# TMS320F28379D_Interfaz.net
KiCad netlist of a schematic drawn in Altium Designer
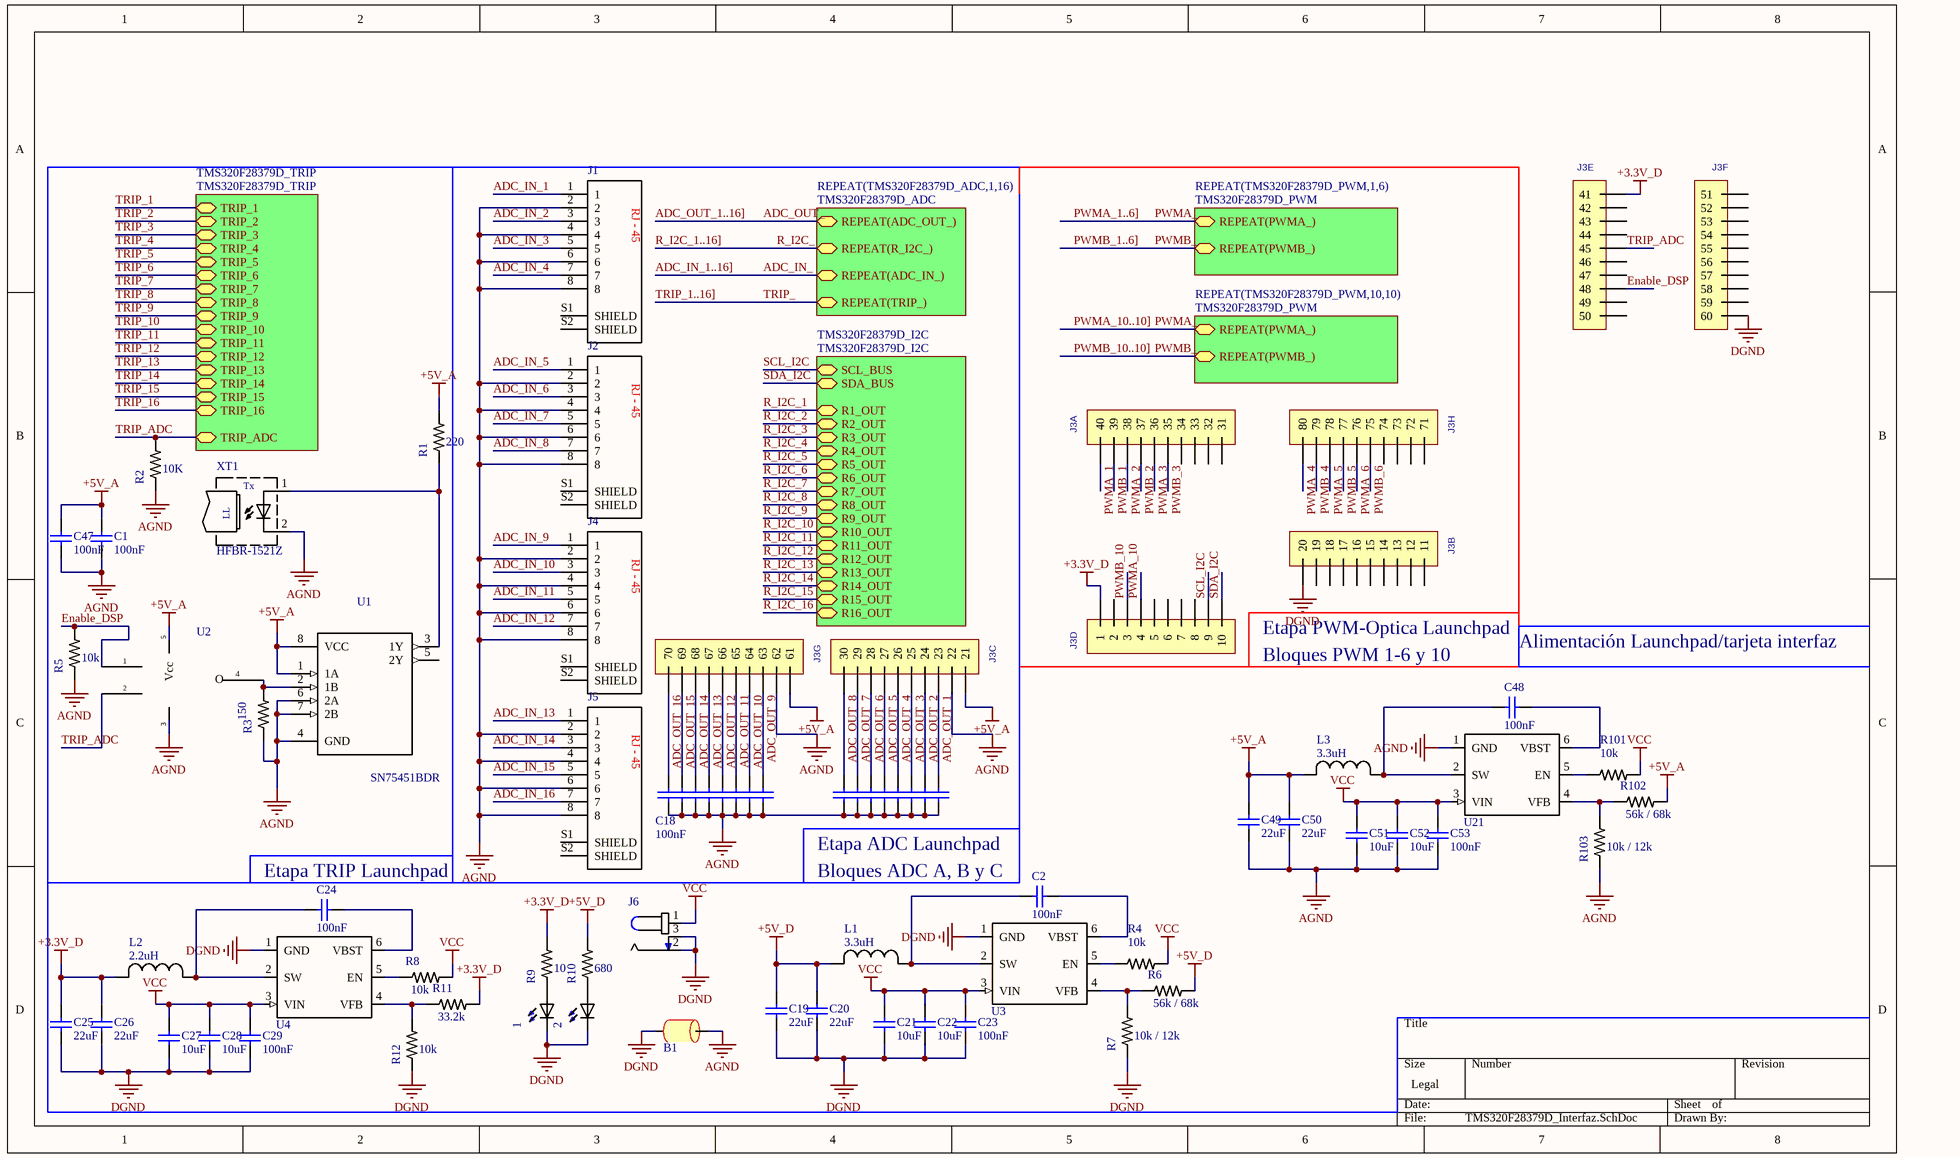
[diagram p0: TMS320F28379D_Interfaz.SchDoc]

(export (version "E")
  (design (tool "Eeschema 10.0.6"))
  (components
    (comp (ref "1")
      (value "LED")
      (footprint "LED_0805")
      (description "Led")
      (fields
        (field (name "DIGI-KEY PART NUMBER") "732-4984-1-ND")
        (field (name "MANUFACTURER PART NUMBER") "150080RS75000")
      )
      (libsource (lib "Fibras Opticas") (part "LED"))
    )
    (comp (ref "2")
      (value "LED")
      (footprint "LED_0805")
      (description "Led")
      (fields
        (field (name "DIGI-KEY PART NUMBER") "732-4984-1-ND")
        (field (name "MANUFACTURER PART NUMBER") "150080RS75000")
      )
      (libsource (lib "Fibras Opticas") (part "LED"))
    )
    (comp (ref "B1")
      (value "Bead")
      (footprint "1206")
      (description "Ferrite bead")
      (fields
        (field (name "DIGI-KEY PART NUMBER") "490-1055-1-ND")
        (field (name "MANUFACTURER PART NUMBER") "BLM31PG500SN1L")
      )
      (libsource (lib "Inductores") (part "Bead"))
    )
    (comp (ref "C1")
      (value "100nF")
      (footprint "CAP 0805")
      (fields (field (name "Comment") "Cap cerámico"))
      (libsource (lib "Condensadores") (part "Cap cerámico"))
    )
    (comp (ref "C2")
      (value "100nF")
      (footprint "CAP 0805")
      (fields (field (name "Comment") "Cap cerámico"))
      (libsource (lib "Condensadores") (part "Cap cerámico"))
    )
    (comp (ref "C3")
      (value "Cap cerámico")
      (footprint "CAP 0805")
      (libsource (lib "Condensadores") (part "Cap cerámico"))
    )
    (comp (ref "C4")
      (value "Cap cerámico")
      (footprint "CAP 0805")
      (libsource (lib "Condensadores") (part "Cap cerámico"))
    )
    (comp (ref "C5")
      (value "Cap cerámico")
      (footprint "CAP 0805")
      (libsource (lib "Condensadores") (part "Cap cerámico"))
    )
    (comp (ref "C6")
      (value "Cap cerámico")
      (footprint "CAP 0805")
      (libsource (lib "Condensadores") (part "Cap cerámico"))
    )
    (comp (ref "C7")
      (value "Cap cerámico")
      (footprint "CAP 0805")
      (libsource (lib "Condensadores") (part "Cap cerámico"))
    )
    (comp (ref "C8")
      (value "Cap cerámico")
      (footprint "CAP 0805")
      (libsource (lib "Condensadores") (part "Cap cerámico"))
    )
    (comp (ref "C9")
      (value "Cap cerámico")
      (footprint "CAP 0805")
      (libsource (lib "Condensadores") (part "Cap cerámico"))
    )
    (comp (ref "C10")
      (value "Cap cerámico")
      (footprint "CAP 0805")
      (libsource (lib "Condensadores") (part "Cap cerámico"))
    )
    (comp (ref "C11")
      (value "Cap cerámico")
      (footprint "CAP 0805")
      (libsource (lib "Condensadores") (part "Cap cerámico"))
    )
    (comp (ref "C12")
      (value "Cap cerámico")
      (footprint "CAP 0805")
      (libsource (lib "Condensadores") (part "Cap cerámico"))
    )
    (comp (ref "C13")
      (value "Cap cerámico")
      (footprint "CAP 0805")
      (libsource (lib "Condensadores") (part "Cap cerámico"))
    )
    (comp (ref "C14")
      (value "Cap cerámico")
      (footprint "CAP 0805")
      (libsource (lib "Condensadores") (part "Cap cerámico"))
    )
    (comp (ref "C15")
      (value "Cap cerámico")
      (footprint "CAP 0805")
      (libsource (lib "Condensadores") (part "Cap cerámico"))
    )
    (comp (ref "C16")
      (value "Cap cerámico")
      (footprint "CAP 0805")
      (libsource (lib "Condensadores") (part "Cap cerámico"))
    )
    (comp (ref "C17")
      (value "Cap cerámico")
      (footprint "CAP 0805")
      (libsource (lib "Condensadores") (part "Cap cerámico"))
    )
    (comp (ref "C18")
      (value "100nF")
      (footprint "CAP 0805")
      (fields (field (name "Comment") "Cap cerámico"))
      (libsource (lib "Condensadores") (part "Cap cerámico"))
    )
    (comp (ref "C19")
      (value "22uF")
      (footprint "CAP 1206")
      (fields (field (name "Comment") "Cap cerámico"))
      (libsource (lib "Condensadores") (part "Cap cerámico"))
    )
    (comp (ref "C20")
      (value "22uF")
      (footprint "CAP 1206")
      (fields (field (name "Comment") "Cap cerámico"))
      (libsource (lib "Condensadores") (part "Cap cerámico"))
    )
    (comp (ref "C21")
      (value "10uF")
      (footprint "CAP 1206")
      (fields (field (name "Comment") "Cap cerámico"))
      (libsource (lib "Condensadores") (part "Cap cerámico"))
    )
    (comp (ref "C22")
      (value "10uF")
      (footprint "CAP 1206")
      (fields (field (name "Comment") "Cap cerámico"))
      (libsource (lib "Condensadores") (part "Cap cerámico"))
    )
    (comp (ref "C23")
      (value "100nF")
      (footprint "CAP 0805")
      (fields (field (name "Comment") "Cap cerámico"))
      (libsource (lib "Condensadores") (part "Cap cerámico"))
    )
    (comp (ref "C24")
      (value "100nF")
      (footprint "CAP 0805")
      (fields (field (name "Comment") "Cap cerámico"))
      (libsource (lib "Condensadores") (part "Cap cerámico"))
    )
    (comp (ref "C25")
      (value "22uF")
      (footprint "CAP 1206")
      (fields (field (name "Comment") "Cap cerámico"))
      (libsource (lib "Condensadores") (part "Cap cerámico"))
    )
    (comp (ref "C26")
      (value "22uF")
      (footprint "CAP 1206")
      (fields (field (name "Comment") "Cap cerámico"))
      (libsource (lib "Condensadores") (part "Cap cerámico"))
    )
    (comp (ref "C27")
      (value "10uF")
      (footprint "CAP 1206")
      (fields (field (name "Comment") "Cap cerámico"))
      (libsource (lib "Condensadores") (part "Cap cerámico"))
    )
    (comp (ref "C28")
      (value "10uF")
      (footprint "CAP 1206")
      (fields (field (name "Comment") "Cap cerámico"))
      (libsource (lib "Condensadores") (part "Cap cerámico"))
    )
    (comp (ref "C29")
      (value "100nF")
      (footprint "CAP 0805")
      (fields (field (name "Comment") "Cap cerámico"))
      (libsource (lib "Condensadores") (part "Cap cerámico"))
    )
    (comp (ref "C47")
      (value "100nF")
      (footprint "CAP 0805")
      (fields (field (name "Comment") "Cap cerámico"))
      (libsource (lib "Condensadores") (part "Cap cerámico"))
    )
    (comp (ref "C48")
      (value "100nF")
      (footprint "CAP 0805")
      (fields (field (name "Comment") "Cap cerámico"))
      (libsource (lib "Condensadores") (part "Cap cerámico"))
    )
    (comp (ref "C49")
      (value "22uF")
      (footprint "CAP 1206")
      (fields (field (name "Comment") "Cap cerámico"))
      (libsource (lib "Condensadores") (part "Cap cerámico"))
    )
    (comp (ref "C50")
      (value "22uF")
      (footprint "CAP 1206")
      (fields (field (name "Comment") "Cap cerámico"))
      (libsource (lib "Condensadores") (part "Cap cerámico"))
    )
    (comp (ref "C51")
      (value "10uF")
      (footprint "CAP 1206")
      (fields (field (name "Comment") "Cap cerámico"))
      (libsource (lib "Condensadores") (part "Cap cerámico"))
    )
    (comp (ref "C52")
      (value "10uF")
      (footprint "CAP 1206")
      (fields (field (name "Comment") "Cap cerámico"))
      (libsource (lib "Condensadores") (part "Cap cerámico"))
    )
    (comp (ref "C53")
      (value "100nF")
      (footprint "CAP 0805")
      (fields (field (name "Comment") "Cap cerámico"))
      (libsource (lib "Condensadores") (part "Cap cerámico"))
    )
    (comp (ref "J1")
      (value "Ethernet TH")
      (footprint "ETHERNET TH")
      (description "CONN MOD JACK 8P8C VERT SHIELDED")
      (fields
        (field (name "DIGI-KEY PART NUMBER") "A31430-ND")
        (field (name "MANUFACTURER PART NUMBER") "5557969-1")
      )
      (libsource (lib "Conectores") (part "Ethernet TH"))
    )
    (comp (ref "J2")
      (value "Ethernet TH")
      (footprint "ETHERNET TH")
      (description "CONN MOD JACK 8P8C VERT SHIELDED")
      (fields
        (field (name "DIGI-KEY PART NUMBER") "A31430-ND")
        (field (name "MANUFACTURER PART NUMBER") "5557969-1")
      )
      (libsource (lib "Conectores") (part "Ethernet TH"))
    )
    (comp (ref "J3")
      (value "Header 20pin")
      (footprint "Header 20pin_TMS320F28379D")
      (fields
        (field (name "DIGI-KEY PART NUMBER") "609-3221-ND")
        (field (name "MANUFACTURER PART NUMBER") "67996-420HLF")
      )
      (libsource (lib "Conectores") (part "Header 20pin"))
    )
    (comp (ref "J4")
      (value "Ethernet TH")
      (footprint "ETHERNET TH")
      (description "CONN MOD JACK 8P8C VERT SHIELDED")
      (fields
        (field (name "DIGI-KEY PART NUMBER") "A31430-ND")
        (field (name "MANUFACTURER PART NUMBER") "5557969-1")
      )
      (libsource (lib "Conectores") (part "Ethernet TH"))
    )
    (comp (ref "J5")
      (value "Ethernet TH")
      (footprint "ETHERNET TH")
      (description "CONN MOD JACK 8P8C VERT SHIELDED")
      (fields
        (field (name "DIGI-KEY PART NUMBER") "A31430-ND")
        (field (name "MANUFACTURER PART NUMBER") "5557969-1")
      )
      (libsource (lib "Conectores") (part "Ethernet TH"))
    )
    (comp (ref "J6")
      (value "694106301002")
      (footprint "Power Jack DC")
      (description "Connector, Power Entry, Jack, 3a, 20vdc")
      (fields (field (name "DIGI-KEY PART NUMBER") "732-5930-ND"))
      (libsource (lib "Conectores") (part "Power Jack"))
    )
    (comp (ref "L1")
      (value "3.3uH")
      (footprint "Inductor 3.3uH")
      (description "Inductor")
      (fields
        (field (name "DIGI-KEY PART NUMBER") "732-1152-1-ND")
        (field (name "MANUFACTURER PART NUMBER") "744311330")
      )
      (libsource (lib "Inductores") (part "Inductor 3.3uH"))
    )
    (comp (ref "L2")
      (value "2.2uH")
      (footprint "Inductor 3.3uH")
      (description "Inductor")
      (fields
        (field (name "DIGI-KEY PART NUMBER") "732-1151-1-ND")
        (field (name "MANUFACTURER PART NUMBER") "744311220")
      )
      (libsource (lib "Inductores") (part "Inductor 2.2uH"))
    )
    (comp (ref "L3")
      (value "3.3uH")
      (footprint "Inductor 3.3uH")
      (description "Inductor")
      (fields
        (field (name "DIGI-KEY PART NUMBER") "732-1152-1-ND")
        (field (name "MANUFACTURER PART NUMBER") "744311330")
      )
      (libsource (lib "Inductores") (part "Inductor 3.3uH"))
    )
    (comp (ref "R1")
      (value "220")
      (footprint "Resistor 0805")
      (description "Resistor")
      (fields (field (name "Comment") "Resistor 0805"))
      (libsource (lib "Resistencias") (part "Resistor"))
    )
    (comp (ref "R2")
      (value "10K")
      (footprint "Resistor 0805")
      (description "Resistor")
      (fields (field (name "Comment") "Resistor 0805"))
      (libsource (lib "Resistencias") (part "Resistor"))
    )
    (comp (ref "R3")
      (value "150")
      (footprint "Resistor 0805")
      (description "Resistor")
      (fields (field (name "Comment") "Resistor 0805"))
      (libsource (lib "Resistencias") (part "Resistor"))
    )
    (comp (ref "R4")
      (value "10k")
      (footprint "Resistor 0805")
      (description "Resistor")
      (fields (field (name "Comment") "Resistor 0805"))
      (libsource (lib "Resistencias") (part "Resistor"))
    )
    (comp (ref "R5")
      (value "10k")
      (footprint "Resistor 0805")
      (description "Resistor")
      (fields (field (name "Comment") "Resistor 0805"))
      (libsource (lib "Resistencias") (part "Resistor"))
    )
    (comp (ref "R6")
      (value "56k / 68k")
      (footprint "Resistor 0805")
      (description "Resistor")
      (fields (field (name "Comment") "Resistor 0805"))
      (libsource (lib "Resistencias") (part "Resistor"))
    )
    (comp (ref "R7")
      (value "10k / 12k")
      (footprint "Resistor 0805")
      (description "Resistor")
      (fields (field (name "Comment") "Resistor 0805"))
      (libsource (lib "Resistencias") (part "Resistor"))
    )
    (comp (ref "R8")
      (value "10k")
      (footprint "Resistor 0805")
      (description "Resistor")
      (fields (field (name "Comment") "Resistor 0805"))
      (libsource (lib "Resistencias") (part "Resistor"))
    )
    (comp (ref "R9")
      (value "10")
      (footprint "Resistor 0805")
      (description "Resistor")
      (fields (field (name "Comment") "Resistor 0805"))
      (libsource (lib "Resistencias") (part "Resistor"))
    )
    (comp (ref "R10")
      (value "680")
      (footprint "Resistor 0805")
      (description "Resistor")
      (fields (field (name "Comment") "Resistor 0805"))
      (libsource (lib "Resistencias") (part "Resistor"))
    )
    (comp (ref "R11")
      (value "33.2k")
      (footprint "Resistor 0805")
      (description "Resistor")
      (fields (field (name "Comment") "Resistor 0805"))
      (libsource (lib "Resistencias") (part "Resistor"))
    )
    (comp (ref "R12")
      (value "10k")
      (footprint "Resistor 0805")
      (description "Resistor")
      (fields (field (name "Comment") "Resistor 0805"))
      (libsource (lib "Resistencias") (part "Resistor"))
    )
    (comp (ref "R101")
      (value "10k")
      (footprint "Resistor 0805")
      (description "Resistor")
      (fields (field (name "Comment") "Resistor 0805"))
      (libsource (lib "Resistencias") (part "Resistor"))
    )
    (comp (ref "R102")
      (value "56k / 68k")
      (footprint "Resistor 0805")
      (description "Resistor")
      (fields (field (name "Comment") "Resistor 0805"))
      (libsource (lib "Resistencias") (part "Resistor"))
    )
    (comp (ref "R103")
      (value "10k / 12k")
      (footprint "Resistor 0805")
      (description "Resistor")
      (fields (field (name "Comment") "Resistor 0805"))
      (libsource (lib "Resistencias") (part "Resistor"))
    )
    (comp (ref "U1")
      (value "SN75451BDR")
      (footprint "8-SOIC")
      (description "Dual Very-High Speed, High-Current Peripheral Drivers 8-SOIC 0 to 70")
      (fields (field (name "DIGI-KEY PART NUMBER") "296-14960-6-ND"))
      (libsource (lib "Circuitos integrados") (part "SN75451BDR"))
    )
    (comp (ref "U2")
      (value "NOR MC74VHC1G02DFT2G")
      (footprint "SOT-553")
      (description "NOR Gate IC 1 Channel SC-88A (SC-70-5/SOT-353)")
      (fields
        (field (name "DIGI-KEY PART NUMBER") "MC74VHC1G02DFT2GOSCT-ND")
        (field (name "MANUFACTURER PART NUMBER") "MC74VHC1G02DFT2G")
      )
      (libsource (lib "Circuitos integrados") (part "NOR MC74VHC1G02DFT2G"))
    )
    (comp (ref "U3")
      (value "TPS565201DDCR")
      (footprint "6-SOT-23")
      (description "Buck 5A")
      (fields (field (name "DIGI-KEY PART NUMBER") "296-49006-1-ND"))
      (libsource (lib "Circuitos integrados") (part "TPS565201DDCR"))
    )
    (comp (ref "U4")
      (value "TPS565201DDCR")
      (footprint "6-SOT-23")
      (description "Buck 5A")
      (fields (field (name "DIGI-KEY PART NUMBER") "296-49006-1-ND"))
      (libsource (lib "Circuitos integrados") (part "TPS565201DDCR"))
    )
    (comp (ref "U21")
      (value "TPS565201DDCR")
      (footprint "6-SOT-23")
      (description "Buck 5A")
      (fields (field (name "DIGI-KEY PART NUMBER") "296-49006-1-ND"))
      (libsource (lib "Circuitos integrados") (part "TPS565201DDCR"))
    )
    (comp (ref "XT1")
      (value "HFBR-1521Z")
      (footprint "HFBR-15X1Z")
      (fields (field (name "DIGI-KEY PART NUMBER") "516-2043-ND"))
      (libsource (lib "Fibras Opticas") (part "HFBR-1521Z"))
    )
  )
  (nets
    (net (code "9") (name "+3.3V_D") (class "Default")
      (node (ref "C25") (pin "2") (pinfunction "2_2") (pintype "passive"))
      (node (ref "C26") (pin "2") (pinfunction "2_2") (pintype "passive"))
      (node (ref "J3") (pin "1") (pinfunction "1_1") (pintype "passive"))
      (node (ref "J3") (pin "41") (pinfunction "41_41") (pintype "passive"))
      (node (ref "L2") (pin "2") (pinfunction "2_2") (pintype "passive"))
      (node (ref "R11") (pin "2") (pinfunction "2_2") (pintype "passive"))
      (node (ref "R9") (pin "2") (pinfunction "2_2") (pintype "passive"))
    )
    (net (code "10") (name "+5V_A") (class "Default")
      (node (ref "C1") (pin "2") (pinfunction "2_2") (pintype "passive"))
      (node (ref "C47") (pin "2") (pinfunction "2_2") (pintype "passive"))
      (node (ref "C49") (pin "2") (pinfunction "2_2") (pintype "passive"))
      (node (ref "C50") (pin "2") (pinfunction "2_2") (pintype "passive"))
      (node (ref "J3") (pin "21") (pinfunction "21_21") (pintype "passive"))
      (node (ref "J3") (pin "61") (pinfunction "61_61") (pintype "passive"))
      (node (ref "L3") (pin "2") (pinfunction "2_2") (pintype "passive"))
      (node (ref "R1") (pin "2") (pinfunction "2_2") (pintype "passive"))
      (node (ref "R102") (pin "2") (pinfunction "2_2") (pintype "passive"))
      (node (ref "U1") (pin "1") (pinfunction "1A_1") (pintype "input"))
      (node (ref "U1") (pin "8") (pinfunction "VCC_8") (pintype "power_in"))
      (node (ref "U2") (pin "5") (pinfunction "Vcc_5") (pintype "passive"))
    )
    (net (code "11") (name "+5V_D") (class "Default")
      (node (ref "C19") (pin "2") (pinfunction "2_2") (pintype "passive"))
      (node (ref "C20") (pin "2") (pinfunction "2_2") (pintype "passive"))
      (node (ref "L1") (pin "2") (pinfunction "2_2") (pintype "passive"))
      (node (ref "R10") (pin "2") (pinfunction "2_2") (pintype "passive"))
      (node (ref "R6") (pin "2") (pinfunction "2_2") (pintype "passive"))
    )
    (net (code "13") (name "/ADC_IN_1") (class "Default")
      (node (ref "J1") (pin "1") (pinfunction "1_1") (pintype "passive"))
    )
    (net (code "14") (name "/ADC_IN_2") (class "Default")
      (node (ref "J1") (pin "3") (pinfunction "3_3") (pintype "passive"))
    )
    (net (code "15") (name "/ADC_IN_3") (class "Default")
      (node (ref "J1") (pin "5") (pinfunction "5_5") (pintype "passive"))
    )
    (net (code "16") (name "/ADC_IN_4") (class "Default")
      (node (ref "J1") (pin "7") (pinfunction "7_7") (pintype "passive"))
    )
    (net (code "17") (name "/ADC_IN_5") (class "Default")
      (node (ref "J2") (pin "1") (pinfunction "1_1") (pintype "passive"))
    )
    (net (code "18") (name "/ADC_IN_6") (class "Default")
      (node (ref "J2") (pin "3") (pinfunction "3_3") (pintype "passive"))
    )
    (net (code "19") (name "/ADC_IN_7") (class "Default")
      (node (ref "J2") (pin "5") (pinfunction "5_5") (pintype "passive"))
    )
    (net (code "20") (name "/ADC_IN_8") (class "Default")
      (node (ref "J2") (pin "7") (pinfunction "7_7") (pintype "passive"))
    )
    (net (code "21") (name "/ADC_IN_9") (class "Default")
      (node (ref "J4") (pin "1") (pinfunction "1_1") (pintype "passive"))
    )
    (net (code "22") (name "/ADC_IN_10") (class "Default")
      (node (ref "J4") (pin "3") (pinfunction "3_3") (pintype "passive"))
    )
    (net (code "23") (name "/ADC_IN_11") (class "Default")
      (node (ref "J4") (pin "5") (pinfunction "5_5") (pintype "passive"))
    )
    (net (code "24") (name "/ADC_IN_12") (class "Default")
      (node (ref "J4") (pin "7") (pinfunction "7_7") (pintype "passive"))
    )
    (net (code "25") (name "/ADC_IN_13") (class "Default")
      (node (ref "J5") (pin "1") (pinfunction "1_1") (pintype "passive"))
    )
    (net (code "26") (name "/ADC_IN_14") (class "Default")
      (node (ref "J5") (pin "3") (pinfunction "3_3") (pintype "passive"))
    )
    (net (code "27") (name "/ADC_IN_15") (class "Default")
      (node (ref "J5") (pin "5") (pinfunction "5_5") (pintype "passive"))
    )
    (net (code "28") (name "/ADC_IN_16") (class "Default")
      (node (ref "J5") (pin "7") (pinfunction "7_7") (pintype "passive"))
    )
    (net (code "30") (name "/ADC_OUT_1") (class "Default")
      (node (ref "C17") (pin "1") (pinfunction "1_1") (pintype "passive"))
      (node (ref "J3") (pin "23") (pinfunction "23_23") (pintype "passive"))
    )
    (net (code "31") (name "/ADC_OUT_2") (class "Default")
      (node (ref "C16") (pin "1") (pinfunction "1_1") (pintype "passive"))
      (node (ref "J3") (pin "24") (pinfunction "24_24") (pintype "passive"))
    )
    (net (code "32") (name "/ADC_OUT_3") (class "Default")
      (node (ref "C15") (pin "1") (pinfunction "1_1") (pintype "passive"))
      (node (ref "J3") (pin "25") (pinfunction "25_25") (pintype "passive"))
    )
    (net (code "33") (name "/ADC_OUT_4") (class "Default")
      (node (ref "C14") (pin "1") (pinfunction "1_1") (pintype "passive"))
      (node (ref "J3") (pin "26") (pinfunction "26_26") (pintype "passive"))
    )
    (net (code "34") (name "/ADC_OUT_5") (class "Default")
      (node (ref "C13") (pin "1") (pinfunction "1_1") (pintype "passive"))
      (node (ref "J3") (pin "27") (pinfunction "27_27") (pintype "passive"))
    )
    (net (code "35") (name "/ADC_OUT_6") (class "Default")
      (node (ref "C12") (pin "1") (pinfunction "1_1") (pintype "passive"))
      (node (ref "J3") (pin "28") (pinfunction "28_28") (pintype "passive"))
    )
    (net (code "36") (name "/ADC_OUT_7") (class "Default")
      (node (ref "C11") (pin "1") (pinfunction "1_1") (pintype "passive"))
      (node (ref "J3") (pin "29") (pinfunction "29_29") (pintype "passive"))
    )
    (net (code "37") (name "/ADC_OUT_8") (class "Default")
      (node (ref "C10") (pin "1") (pinfunction "1_1") (pintype "passive"))
      (node (ref "J3") (pin "30") (pinfunction "30_30") (pintype "passive"))
    )
    (net (code "38") (name "/ADC_OUT_9") (class "Default")
      (node (ref "C9") (pin "1") (pinfunction "1_1") (pintype "passive"))
      (node (ref "J3") (pin "63") (pinfunction "63_63") (pintype "passive"))
    )
    (net (code "39") (name "/ADC_OUT_10") (class "Default")
      (node (ref "C8") (pin "1") (pinfunction "1_1") (pintype "passive"))
      (node (ref "J3") (pin "64") (pinfunction "64_64") (pintype "passive"))
    )
    (net (code "40") (name "/ADC_OUT_11") (class "Default")
      (node (ref "C7") (pin "1") (pinfunction "1_1") (pintype "passive"))
      (node (ref "J3") (pin "65") (pinfunction "65_65") (pintype "passive"))
    )
    (net (code "41") (name "/ADC_OUT_12") (class "Default")
      (node (ref "C6") (pin "1") (pinfunction "1_1") (pintype "passive"))
      (node (ref "J3") (pin "66") (pinfunction "66_66") (pintype "passive"))
    )
    (net (code "42") (name "/ADC_OUT_13") (class "Default")
      (node (ref "C5") (pin "1") (pinfunction "1_1") (pintype "passive"))
      (node (ref "J3") (pin "67") (pinfunction "67_67") (pintype "passive"))
    )
    (net (code "43") (name "/ADC_OUT_14") (class "Default")
      (node (ref "C4") (pin "1") (pinfunction "1_1") (pintype "passive"))
      (node (ref "J3") (pin "68") (pinfunction "68_68") (pintype "passive"))
    )
    (net (code "44") (name "/ADC_OUT_15") (class "Default")
      (node (ref "C3") (pin "1") (pinfunction "1_1") (pintype "passive"))
      (node (ref "J3") (pin "69") (pinfunction "69_69") (pintype "passive"))
    )
    (net (code "45") (name "/ADC_OUT_16") (class "Default")
      (node (ref "C18") (pin "2") (pinfunction "2_2") (pintype "passive"))
      (node (ref "J3") (pin "70") (pinfunction "70_70") (pintype "passive"))
    )
    (net (code "46") (name "/Enable_DSP") (class "Default")
      (node (ref "J3") (pin "48") (pinfunction "48_48") (pintype "passive"))
      (node (ref "R5") (pin "2") (pinfunction "2_2") (pintype "passive"))
      (node (ref "U2") (pin "1") (pinfunction "1_1") (pintype "passive"))
    )
    (net (code "48") (name "/PWMA_1") (class "Default")
      (node (ref "J3") (pin "40") (pinfunction "40_40") (pintype "passive"))
    )
    (net (code "49") (name "/PWMA_2") (class "Default")
      (node (ref "J3") (pin "38") (pinfunction "38_38") (pintype "passive"))
    )
    (net (code "50") (name "/PWMA_3") (class "Default")
      (node (ref "J3") (pin "36") (pinfunction "36_36") (pintype "passive"))
    )
    (net (code "51") (name "/PWMA_4") (class "Default")
      (node (ref "J3") (pin "80") (pinfunction "80_80") (pintype "passive"))
    )
    (net (code "52") (name "/PWMA_5") (class "Default")
      (node (ref "J3") (pin "78") (pinfunction "78_78") (pintype "passive"))
    )
    (net (code "53") (name "/PWMA_6") (class "Default")
      (node (ref "J3") (pin "76") (pinfunction "76_76") (pintype "passive"))
    )
    (net (code "54") (name "/PWMA_10") (class "Default")
      (node (ref "J3") (pin "4") (pinfunction "4_4") (pintype "passive"))
    )
    (net (code "56") (name "/PWMB_1") (class "Default")
      (node (ref "J3") (pin "39") (pinfunction "39_39") (pintype "passive"))
    )
    (net (code "57") (name "/PWMB_2") (class "Default")
      (node (ref "J3") (pin "37") (pinfunction "37_37") (pintype "passive"))
    )
    (net (code "58") (name "/PWMB_3") (class "Default")
      (node (ref "J3") (pin "35") (pinfunction "35_35") (pintype "passive"))
    )
    (net (code "59") (name "/PWMB_4") (class "Default")
      (node (ref "J3") (pin "79") (pinfunction "79_79") (pintype "passive"))
    )
    (net (code "60") (name "/PWMB_5") (class "Default")
      (node (ref "J3") (pin "77") (pinfunction "77_77") (pintype "passive"))
    )
    (net (code "61") (name "/PWMB_6") (class "Default")
      (node (ref "J3") (pin "75") (pinfunction "75_75") (pintype "passive"))
    )
    (net (code "62") (name "/PWMB_10") (class "Default")
      (node (ref "J3") (pin "3") (pinfunction "3_3") (pintype "passive"))
    )
    (net (code "80") (name "/SCL_I2C") (class "Default")
      (node (ref "J3") (pin "9") (pinfunction "9_9") (pintype "passive"))
    )
    (net (code "81") (name "/SDA_I2C") (class "Default")
      (node (ref "J3") (pin "10") (pinfunction "10_10") (pintype "passive"))
    )
    (net (code "99") (name "/TRIP_ADC") (class "Default")
      (node (ref "J3") (pin "45") (pinfunction "45_45") (pintype "passive"))
      (node (ref "R2") (pin "2") (pinfunction "2_2") (pintype "passive"))
      (node (ref "U2") (pin "2") (pinfunction "2_2") (pintype "passive"))
    )
    (net (code "108") (name "AGND") (class "Default")
      (node (ref "B1") (pin "1") (pintype "passive"))
      (node (ref "C1") (pin "1") (pinfunction "1_1") (pintype "passive"))
      (node (ref "C10") (pin "2") (pinfunction "2_2") (pintype "passive"))
      (node (ref "C11") (pin "2") (pinfunction "2_2") (pintype "passive"))
      (node (ref "C12") (pin "2") (pinfunction "2_2") (pintype "passive"))
      (node (ref "C13") (pin "2") (pinfunction "2_2") (pintype "passive"))
      (node (ref "C14") (pin "2") (pinfunction "2_2") (pintype "passive"))
      (node (ref "C15") (pin "2") (pinfunction "2_2") (pintype "passive"))
      (node (ref "C16") (pin "2") (pinfunction "2_2") (pintype "passive"))
      (node (ref "C17") (pin "2") (pinfunction "2_2") (pintype "passive"))
      (node (ref "C18") (pin "1") (pinfunction "1_1") (pintype "passive"))
      (node (ref "C3") (pin "2") (pinfunction "2_2") (pintype "passive"))
      (node (ref "C4") (pin "2") (pinfunction "2_2") (pintype "passive"))
      (node (ref "C47") (pin "1") (pinfunction "1_1") (pintype "passive"))
      (node (ref "C49") (pin "1") (pinfunction "1_1") (pintype "passive"))
      (node (ref "C5") (pin "2") (pinfunction "2_2") (pintype "passive"))
      (node (ref "C50") (pin "1") (pinfunction "1_1") (pintype "passive"))
      (node (ref "C51") (pin "2") (pinfunction "2_2") (pintype "passive"))
      (node (ref "C52") (pin "2") (pinfunction "2_2") (pintype "passive"))
      (node (ref "C53") (pin "2") (pinfunction "2_2") (pintype "passive"))
      (node (ref "C6") (pin "2") (pinfunction "2_2") (pintype "passive"))
      (node (ref "C7") (pin "2") (pinfunction "2_2") (pintype "passive"))
      (node (ref "C8") (pin "2") (pinfunction "2_2") (pintype "passive"))
      (node (ref "C9") (pin "2") (pinfunction "2_2") (pintype "passive"))
      (node (ref "J1") (pin "2") (pinfunction "2_2") (pintype "passive"))
      (node (ref "J1") (pin "4") (pinfunction "4_4") (pintype "passive"))
      (node (ref "J1") (pin "6") (pinfunction "6_6") (pintype "passive"))
      (node (ref "J1") (pin "8") (pinfunction "8_8") (pintype "passive"))
      (node (ref "J2") (pin "2") (pinfunction "2_2") (pintype "passive"))
      (node (ref "J2") (pin "4") (pinfunction "4_4") (pintype "passive"))
      (node (ref "J2") (pin "6") (pinfunction "6_6") (pintype "passive"))
      (node (ref "J2") (pin "8") (pinfunction "8_8") (pintype "passive"))
      (node (ref "J3") (pin "22") (pinfunction "22_22") (pintype "passive"))
      (node (ref "J3") (pin "62") (pinfunction "62_62") (pintype "passive"))
      (node (ref "J4") (pin "2") (pinfunction "2_2") (pintype "passive"))
      (node (ref "J4") (pin "4") (pinfunction "4_4") (pintype "passive"))
      (node (ref "J4") (pin "6") (pinfunction "6_6") (pintype "passive"))
      (node (ref "J4") (pin "8") (pinfunction "8_8") (pintype "passive"))
      (node (ref "J5") (pin "2") (pinfunction "2_2") (pintype "passive"))
      (node (ref "J5") (pin "4") (pinfunction "4_4") (pintype "passive"))
      (node (ref "J5") (pin "6") (pinfunction "6_6") (pintype "passive"))
      (node (ref "J5") (pin "8") (pinfunction "8_8") (pintype "passive"))
      (node (ref "R103") (pin "1") (pinfunction "1_1") (pintype "passive"))
      (node (ref "R2") (pin "1") (pinfunction "1_1") (pintype "passive"))
      (node (ref "R3") (pin "1") (pinfunction "1_1") (pintype "passive"))
      (node (ref "R5") (pin "1") (pinfunction "1_1") (pintype "passive"))
      (node (ref "U1") (pin "4") (pinfunction "GND_4") (pintype "passive"))
      (node (ref "U1") (pin "6") (pinfunction "2A_6") (pintype "input"))
      (node (ref "U1") (pin "7") (pinfunction "2B_7") (pintype "input"))
      (node (ref "U2") (pin "3") (pinfunction "GND_3") (pintype "passive"))
      (node (ref "U21") (pin "1") (pinfunction "GND_1") (pintype "bidirectional"))
      (node (ref "XT1") (pin "2") (pinfunction "C_2") (pintype "passive"))
    )
    (net (code "109") (name "DGND") (class "Default")
      (node (ref "1") (pin "1") (pinfunction "NEG_1") (pintype "passive"))
      (node (ref "2") (pin "1") (pinfunction "NEG_1") (pintype "passive"))
      (node (ref "B1") (pin "2") (pintype "passive"))
      (node (ref "C19") (pin "1") (pinfunction "1_1") (pintype "passive"))
      (node (ref "C20") (pin "1") (pinfunction "1_1") (pintype "passive"))
      (node (ref "C21") (pin "2") (pinfunction "2_2") (pintype "passive"))
      (node (ref "C22") (pin "2") (pinfunction "2_2") (pintype "passive"))
      (node (ref "C23") (pin "2") (pinfunction "2_2") (pintype "passive"))
      (node (ref "C25") (pin "1") (pinfunction "1_1") (pintype "passive"))
      (node (ref "C26") (pin "1") (pinfunction "1_1") (pintype "passive"))
      (node (ref "C27") (pin "2") (pinfunction "2_2") (pintype "passive"))
      (node (ref "C28") (pin "2") (pinfunction "2_2") (pintype "passive"))
      (node (ref "C29") (pin "2") (pinfunction "2_2") (pintype "passive"))
      (node (ref "J3") (pin "20") (pinfunction "20_20") (pintype "passive"))
      (node (ref "J3") (pin "60") (pinfunction "60_60") (pintype "passive"))
      (node (ref "J6") (pin "2") (pinfunction "2_2") (pintype "passive"))
      (node (ref "J6") (pin "3") (pinfunction "3_3") (pintype "passive"))
      (node (ref "R12") (pin "1") (pinfunction "1_1") (pintype "passive"))
      (node (ref "R7") (pin "1") (pinfunction "1_1") (pintype "passive"))
      (node (ref "U3") (pin "1") (pinfunction "GND_1") (pintype "bidirectional"))
      (node (ref "U4") (pin "1") (pinfunction "GND_1") (pintype "bidirectional"))
    )
    (net (code "110") (name "Net-(1-POS)") (class "Default")
      (node (ref "1") (pin "2") (pinfunction "POS_2") (pintype "passive"))
      (node (ref "R9") (pin "1") (pinfunction "1_1") (pintype "passive"))
    )
    (net (code "111") (name "Net-(2-POS)") (class "Default")
      (node (ref "2") (pin "2") (pinfunction "POS_2") (pintype "passive"))
      (node (ref "R10") (pin "1") (pinfunction "1_1") (pintype "passive"))
    )
    (net (code "112") (name "Net-(U1-1B)") (class "Default")
      (node (ref "R3") (pin "2") (pinfunction "2_2") (pintype "passive"))
      (node (ref "U1") (pin "2") (pinfunction "1B_2") (pintype "input"))
      (node (ref "U2") (pin "4") (pinfunction "4_4") (pintype "passive"))
    )
    (net (code "113") (name "Net-(U1-1Y)") (class "Default")
      (node (ref "R1") (pin "1") (pinfunction "1_1") (pintype "passive"))
      (node (ref "U1") (pin "3") (pinfunction "1Y_3") (pintype "output"))
      (node (ref "XT1") (pin "1") (pinfunction "A_1") (pintype "passive"))
    )
    (net (code "114") (name "Net-(U3-EN)") (class "Default")
      (node (ref "R4") (pin "1") (pinfunction "1_1") (pintype "passive"))
      (node (ref "U3") (pin "5") (pinfunction "EN_5") (pintype "bidirectional"))
    )
    (net (code "115") (name "Net-(U3-SW)") (class "Default")
      (node (ref "C2") (pin "1") (pinfunction "1_1") (pintype "passive"))
      (node (ref "L1") (pin "1") (pinfunction "1_1") (pintype "passive"))
      (node (ref "U3") (pin "2") (pinfunction "SW_2") (pintype "bidirectional"))
    )
    (net (code "116") (name "Net-(U3-VBST)") (class "Default")
      (node (ref "C2") (pin "2") (pinfunction "2_2") (pintype "passive"))
      (node (ref "U3") (pin "6") (pinfunction "VBST_6") (pintype "bidirectional"))
    )
    (net (code "117") (name "Net-(U3-VFB)") (class "Default")
      (node (ref "R6") (pin "1") (pinfunction "1_1") (pintype "passive"))
      (node (ref "R7") (pin "2") (pinfunction "2_2") (pintype "passive"))
      (node (ref "U3") (pin "4") (pinfunction "VFB_4") (pintype "bidirectional"))
    )
    (net (code "118") (name "Net-(U4-EN)") (class "Default")
      (node (ref "R8") (pin "1") (pinfunction "1_1") (pintype "passive"))
      (node (ref "U4") (pin "5") (pinfunction "EN_5") (pintype "bidirectional"))
    )
    (net (code "119") (name "Net-(U4-SW)") (class "Default")
      (node (ref "C24") (pin "1") (pinfunction "1_1") (pintype "passive"))
      (node (ref "L2") (pin "1") (pinfunction "1_1") (pintype "passive"))
      (node (ref "U4") (pin "2") (pinfunction "SW_2") (pintype "bidirectional"))
    )
    (net (code "120") (name "Net-(U4-VBST)") (class "Default")
      (node (ref "C24") (pin "2") (pinfunction "2_2") (pintype "passive"))
      (node (ref "U4") (pin "6") (pinfunction "VBST_6") (pintype "bidirectional"))
    )
    (net (code "121") (name "Net-(U4-VFB)") (class "Default")
      (node (ref "R11") (pin "1") (pinfunction "1_1") (pintype "passive"))
      (node (ref "R12") (pin "2") (pinfunction "2_2") (pintype "passive"))
      (node (ref "U4") (pin "4") (pinfunction "VFB_4") (pintype "bidirectional"))
    )
    (net (code "122") (name "Net-(U21-EN)") (class "Default")
      (node (ref "R101") (pin "1") (pinfunction "1_1") (pintype "passive"))
      (node (ref "U21") (pin "5") (pinfunction "EN_5") (pintype "bidirectional"))
    )
    (net (code "123") (name "Net-(U21-SW)") (class "Default")
      (node (ref "C48") (pin "1") (pinfunction "1_1") (pintype "passive"))
      (node (ref "L3") (pin "1") (pinfunction "1_1") (pintype "passive"))
      (node (ref "U21") (pin "2") (pinfunction "SW_2") (pintype "bidirectional"))
    )
    (net (code "124") (name "Net-(U21-VBST)") (class "Default")
      (node (ref "C48") (pin "2") (pinfunction "2_2") (pintype "passive"))
      (node (ref "U21") (pin "6") (pinfunction "VBST_6") (pintype "bidirectional"))
    )
    (net (code "125") (name "Net-(U21-VFB)") (class "Default")
      (node (ref "R102") (pin "1") (pinfunction "1_1") (pintype "passive"))
      (node (ref "R103") (pin "2") (pinfunction "2_2") (pintype "passive"))
      (node (ref "U21") (pin "4") (pinfunction "VFB_4") (pintype "bidirectional"))
    )
    (net (code "126") (name "VCC") (class "Default")
      (node (ref "C21") (pin "1") (pinfunction "1_1") (pintype "passive"))
      (node (ref "C22") (pin "1") (pinfunction "1_1") (pintype "passive"))
      (node (ref "C23") (pin "1") (pinfunction "1_1") (pintype "passive"))
      (node (ref "C27") (pin "1") (pinfunction "1_1") (pintype "passive"))
      (node (ref "C28") (pin "1") (pinfunction "1_1") (pintype "passive"))
      (node (ref "C29") (pin "1") (pinfunction "1_1") (pintype "passive"))
      (node (ref "C51") (pin "1") (pinfunction "1_1") (pintype "passive"))
      (node (ref "C52") (pin "1") (pinfunction "1_1") (pintype "passive"))
      (node (ref "C53") (pin "1") (pinfunction "1_1") (pintype "passive"))
      (node (ref "J6") (pin "1") (pinfunction "1_1") (pintype "passive"))
      (node (ref "R101") (pin "2") (pinfunction "2_2") (pintype "passive"))
      (node (ref "R4") (pin "2") (pinfunction "2_2") (pintype "passive"))
      (node (ref "R8") (pin "2") (pinfunction "2_2") (pintype "passive"))
      (node (ref "U21") (pin "3") (pinfunction "VIN_3") (pintype "input"))
      (node (ref "U3") (pin "3") (pinfunction "VIN_3") (pintype "input"))
      (node (ref "U4") (pin "3") (pinfunction "VIN_3") (pintype "input"))
    )
    (net (code "127") (name "unconnected-(J1-SHIELD-PadS1)") (class "Default")
      (node (ref "J1") (pin "S1") (pinfunction "SHIELD_S1") (pintype "passive"))
    )
    (net (code "128") (name "unconnected-(J1-SHIELD-PadS2)") (class "Default")
      (node (ref "J1") (pin "S2") (pinfunction "SHIELD_S2") (pintype "passive"))
    )
    (net (code "129") (name "unconnected-(J2-SHIELD-PadS1)") (class "Default")
      (node (ref "J2") (pin "S1") (pinfunction "SHIELD_S1") (pintype "passive"))
    )
    (net (code "130") (name "unconnected-(J2-SHIELD-PadS2)") (class "Default")
      (node (ref "J2") (pin "S2") (pinfunction "SHIELD_S2") (pintype "passive"))
    )
    (net (code "131") (name "unconnected-(J3-Pad2)") (class "Default")
      (node (ref "J3") (pin "2") (pinfunction "2_2") (pintype "passive"))
    )
    (net (code "132") (name "unconnected-(J3-Pad5)") (class "Default")
      (node (ref "J3") (pin "5") (pinfunction "5_5") (pintype "passive"))
    )
    (net (code "133") (name "unconnected-(J3-Pad6)") (class "Default")
      (node (ref "J3") (pin "6") (pinfunction "6_6") (pintype "passive"))
    )
    (net (code "134") (name "unconnected-(J3-Pad7)") (class "Default")
      (node (ref "J3") (pin "7") (pinfunction "7_7") (pintype "passive"))
    )
    (net (code "135") (name "unconnected-(J3-Pad8)") (class "Default")
      (node (ref "J3") (pin "8") (pinfunction "8_8") (pintype "passive"))
    )
    (net (code "136") (name "unconnected-(J3-Pad11)") (class "Default")
      (node (ref "J3") (pin "11") (pinfunction "11_11") (pintype "passive"))
    )
    (net (code "137") (name "unconnected-(J3-Pad12)") (class "Default")
      (node (ref "J3") (pin "12") (pinfunction "12_12") (pintype "passive"))
    )
    (net (code "138") (name "unconnected-(J3-Pad13)") (class "Default")
      (node (ref "J3") (pin "13") (pinfunction "13_13") (pintype "passive"))
    )
    (net (code "139") (name "unconnected-(J3-Pad14)") (class "Default")
      (node (ref "J3") (pin "14") (pinfunction "14_14") (pintype "passive"))
    )
    (net (code "140") (name "unconnected-(J3-Pad15)") (class "Default")
      (node (ref "J3") (pin "15") (pinfunction "15_15") (pintype "passive"))
    )
    (net (code "141") (name "unconnected-(J3-Pad16)") (class "Default")
      (node (ref "J3") (pin "16") (pinfunction "16_16") (pintype "passive"))
    )
    (net (code "142") (name "unconnected-(J3-Pad17)") (class "Default")
      (node (ref "J3") (pin "17") (pinfunction "17_17") (pintype "passive"))
    )
    (net (code "143") (name "unconnected-(J3-Pad18)") (class "Default")
      (node (ref "J3") (pin "18") (pinfunction "18_18") (pintype "passive"))
    )
    (net (code "144") (name "unconnected-(J3-Pad19)") (class "Default")
      (node (ref "J3") (pin "19") (pinfunction "19_19") (pintype "passive"))
    )
    (net (code "145") (name "unconnected-(J3-Pad31)") (class "Default")
      (node (ref "J3") (pin "31") (pinfunction "31_31") (pintype "passive"))
    )
    (net (code "146") (name "unconnected-(J3-Pad32)") (class "Default")
      (node (ref "J3") (pin "32") (pinfunction "32_32") (pintype "passive"))
    )
    (net (code "147") (name "unconnected-(J3-Pad33)") (class "Default")
      (node (ref "J3") (pin "33") (pinfunction "33_33") (pintype "passive"))
    )
    (net (code "148") (name "unconnected-(J3-Pad34)") (class "Default")
      (node (ref "J3") (pin "34") (pinfunction "34_34") (pintype "passive"))
    )
    (net (code "149") (name "unconnected-(J3-Pad42)") (class "Default")
      (node (ref "J3") (pin "42") (pinfunction "42_42") (pintype "passive"))
    )
    (net (code "150") (name "unconnected-(J3-Pad43)") (class "Default")
      (node (ref "J3") (pin "43") (pinfunction "43_43") (pintype "passive"))
    )
    (net (code "151") (name "unconnected-(J3-Pad44)") (class "Default")
      (node (ref "J3") (pin "44") (pinfunction "44_44") (pintype "passive"))
    )
    (net (code "152") (name "unconnected-(J3-Pad46)") (class "Default")
      (node (ref "J3") (pin "46") (pinfunction "46_46") (pintype "passive"))
    )
    (net (code "153") (name "unconnected-(J3-Pad47)") (class "Default")
      (node (ref "J3") (pin "47") (pinfunction "47_47") (pintype "passive"))
    )
    (net (code "154") (name "unconnected-(J3-Pad49)") (class "Default")
      (node (ref "J3") (pin "49") (pinfunction "49_49") (pintype "passive"))
    )
    (net (code "155") (name "unconnected-(J3-Pad50)") (class "Default")
      (node (ref "J3") (pin "50") (pinfunction "50_50") (pintype "passive"))
    )
    (net (code "156") (name "unconnected-(J3-Pad51)") (class "Default")
      (node (ref "J3") (pin "51") (pinfunction "51_51") (pintype "passive"))
    )
    (net (code "157") (name "unconnected-(J3-Pad52)") (class "Default")
      (node (ref "J3") (pin "52") (pinfunction "52_52") (pintype "passive"))
    )
    (net (code "158") (name "unconnected-(J3-Pad53)") (class "Default")
      (node (ref "J3") (pin "53") (pinfunction "53_53") (pintype "passive"))
    )
    (net (code "159") (name "unconnected-(J3-Pad54)") (class "Default")
      (node (ref "J3") (pin "54") (pinfunction "54_54") (pintype "passive"))
    )
    (net (code "160") (name "unconnected-(J3-Pad55)") (class "Default")
      (node (ref "J3") (pin "55") (pinfunction "55_55") (pintype "passive"))
    )
    (net (code "161") (name "unconnected-(J3-Pad56)") (class "Default")
      (node (ref "J3") (pin "56") (pinfunction "56_56") (pintype "passive"))
    )
    (net (code "162") (name "unconnected-(J3-Pad57)") (class "Default")
      (node (ref "J3") (pin "57") (pinfunction "57_57") (pintype "passive"))
    )
    (net (code "163") (name "unconnected-(J3-Pad58)") (class "Default")
      (node (ref "J3") (pin "58") (pinfunction "58_58") (pintype "passive"))
    )
    (net (code "164") (name "unconnected-(J3-Pad59)") (class "Default")
      (node (ref "J3") (pin "59") (pinfunction "59_59") (pintype "passive"))
    )
    (net (code "165") (name "unconnected-(J3-Pad71)") (class "Default")
      (node (ref "J3") (pin "71") (pinfunction "71_71") (pintype "passive"))
    )
    (net (code "166") (name "unconnected-(J3-Pad72)") (class "Default")
      (node (ref "J3") (pin "72") (pinfunction "72_72") (pintype "passive"))
    )
    (net (code "167") (name "unconnected-(J3-Pad73)") (class "Default")
      (node (ref "J3") (pin "73") (pinfunction "73_73") (pintype "passive"))
    )
    (net (code "168") (name "unconnected-(J3-Pad74)") (class "Default")
      (node (ref "J3") (pin "74") (pinfunction "74_74") (pintype "passive"))
    )
    (net (code "169") (name "unconnected-(J4-SHIELD-PadS1)") (class "Default")
      (node (ref "J4") (pin "S1") (pinfunction "SHIELD_S1") (pintype "passive"))
    )
    (net (code "170") (name "unconnected-(J4-SHIELD-PadS2)") (class "Default")
      (node (ref "J4") (pin "S2") (pinfunction "SHIELD_S2") (pintype "passive"))
    )
    (net (code "171") (name "unconnected-(J5-SHIELD-PadS1)") (class "Default")
      (node (ref "J5") (pin "S1") (pinfunction "SHIELD_S1") (pintype "passive"))
    )
    (net (code "172") (name "unconnected-(J5-SHIELD-PadS2)") (class "Default")
      (node (ref "J5") (pin "S2") (pinfunction "SHIELD_S2") (pintype "passive"))
    )
    (net (code "173") (name "unconnected-(U1-2Y-Pad5)") (class "Default")
      (node (ref "U1") (pin "5") (pinfunction "2Y_5") (pintype "output"))
    )
  )
)
